# SCH_MSP430G2553-protoboard.net
KiCad netlist of a schematic drawn in EasyEDA
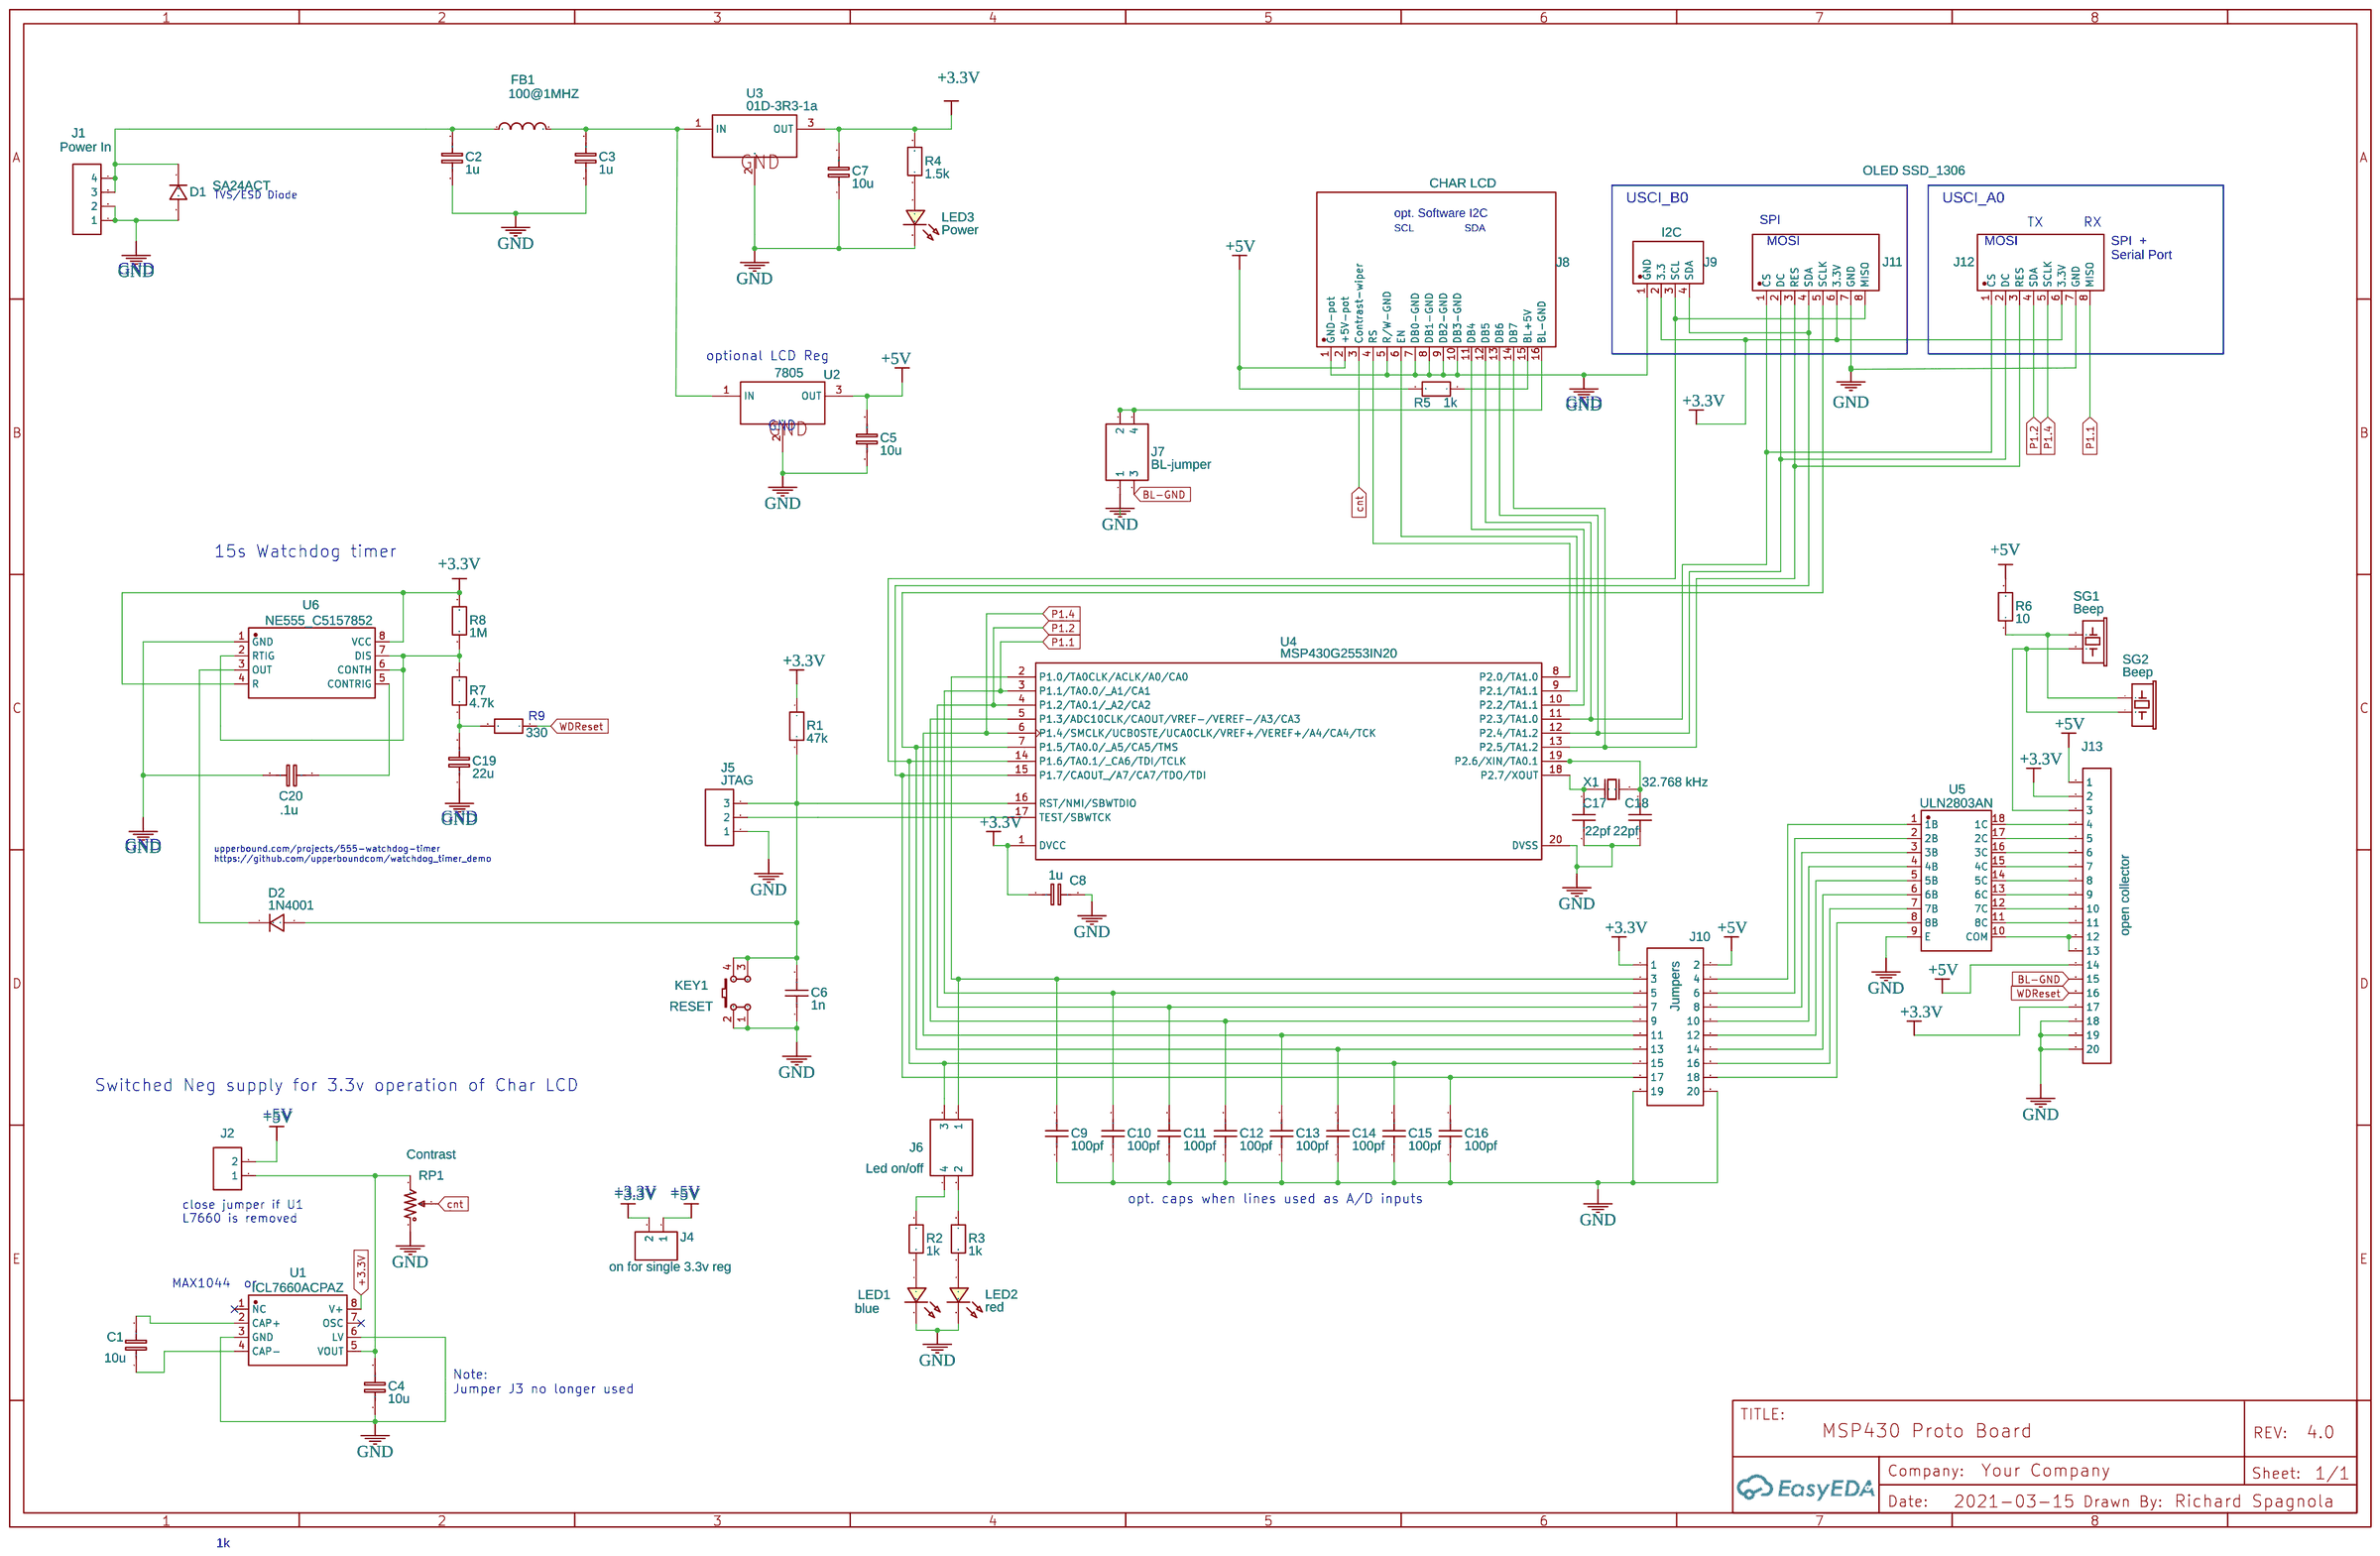
[diagram p0: schematic sheet]

(export (version "E")
  (design (tool "Eeschema 10.0.6"))
  (components
    (comp (ref "C1") (value "10u") (libsource (lib "") (part "C_RAD-0.2_EU_3")))
    (comp (ref "C2") (value "1u") (libsource (lib "") (part "C_RAD-0.2_EU")))
    (comp (ref "C3") (value "1u") (libsource (lib "") (part "C_RAD-0.2_EU")))
    (comp (ref "C4") (value "10u") (libsource (lib "") (part "C_RAD-0.2_EU")))
    (comp (ref "C5") (value "10u") (libsource (lib "") (part "C_RAD-0.2_EU_2")))
    (comp (ref "C6") (value "1n") (libsource (lib "") (part "C_RAD-0.1_US")))
    (comp (ref "C7") (value "10u") (libsource (lib "") (part "C_RAD-0.2_EU_2")))
    (comp (ref "C8") (value "1u") (libsource (lib "") (part "C_RAD-0.2_EU_4")))
    (comp (ref "C9") (value "100pf") (libsource (lib "") (part "C_RAD-0.1_US")))
    (comp (ref "C10") (value "100pf") (libsource (lib "") (part "C_RAD-0.1_US")))
    (comp (ref "C11") (value "100pf") (libsource (lib "") (part "C_RAD-0.1_US")))
    (comp (ref "C12") (value "100pf") (libsource (lib "") (part "C_RAD-0.1_US")))
    (comp (ref "C13") (value "100pf") (libsource (lib "") (part "C_RAD-0.1_US")))
    (comp (ref "C14") (value "100pf") (libsource (lib "") (part "C_RAD-0.1_US")))
    (comp (ref "C15") (value "100pf") (libsource (lib "") (part "C_RAD-0.1_US")))
    (comp (ref "C16") (value "100pf") (libsource (lib "") (part "C_RAD-0.1_US")))
    (comp (ref "C17") (value "22pf") (libsource (lib "") (part "C_RAD-0.1_US_1")))
    (comp (ref "C18") (value "22pf") (libsource (lib "") (part "C_RAD-0.1_US")))
    (comp (ref "C19") (value "22u") (libsource (lib "") (part "C_RAD-0.2_EU")))
    (comp (ref "C20") (value ".1u") (libsource (lib "") (part "C_RAD-0.2_EU_1")))
    (comp (ref "D1")
      (value "SA24ACT")
      (fields (field (name "BOM_Manufacturer Part") "1N4007") (field (name "BOM_Supplier Part") "C106903"))
      (libsource (lib "") (part "1N4007_1"))
    )
    (comp (ref "D2")
      (value "1N4001")
      (fields (field (name "BOM_Manufacturer Part") "1N4007") (field (name "BOM_Supplier Part") "C106903"))
      (libsource (lib "") (part "1N4007"))
    )
    (comp (ref "FB1")
      (value "100@1MHZ")
      (fields
        (field (name "BOM_Manufacturer Part") "MLB6*10-3T(f)")
        (field (name "BOM_Supplier Part") "C59501")
      )
      (libsource (lib "") (part "6Hole beads6*10-3T"))
    )
    (comp (ref "J1")
      (value "Power In")
      (fields (field (name "BOM_Supplier Part") "C124378"))
      (libsource (lib "") (part "HDR-M-2.54_1x4"))
    )
    (comp (ref "J2")
      (value "HDR-M-2.54_1x2")
      (fields (field (name "BOM_Supplier Part") "C124375"))
      (libsource (lib "") (part "HDR-M-2.54_1x2_1"))
    )
    (comp (ref "J4")
      (value "on for single 3.3v reg")
      (fields (field (name "BOM_Supplier Part") "C124375"))
      (libsource (lib "") (part "HDR-M-2.54_1x2"))
    )
    (comp (ref "J5")
      (value "JTAG")
      (fields (field (name "BOM_Supplier Part") "C180248"))
      (libsource (lib "") (part "HDR-M-2.54_1x3"))
    )
    (comp (ref "J6")
      (value "Led on/off")
      (fields (field (name "BOM_Supplier Part") "C66690"))
      (libsource (lib "") (part "HDR-M-2.54_2x2_1"))
    )
    (comp (ref "J7")
      (value "BL-jumper")
      (fields (field (name "BOM_Supplier Part") "C66690"))
      (libsource (lib "") (part "HDR-M-2.54_2x2"))
    )
    (comp (ref "J8") (value "CHAR LCD") (libsource (lib "") (part "LCD")))
    (comp (ref "J9") (value "I2C") (libsource (lib "") (part "I2C")))
    (comp (ref "J10")
      (value "Jumpers")
      (fields (field (name "BOM_Supplier Part") "C124359"))
      (libsource (lib "") (part "HDR-M-2.54_2x10"))
    )
    (comp (ref "J11") (value "OLED SSD_1306") (libsource (lib "") (part "SSD_1306")))
    (comp (ref "J12") (value "OLED SSD_1306") (libsource (lib "") (part "SSD_1306")))
    (comp (ref "J13")
      (value "open collector")
      (fields (field (name "BOM_Supplier Part") "C50981"))
      (libsource (lib "") (part "HDR-M-2.54_1x20"))
    )
    (comp (ref "KEY1")
      (value "RESET")
      (fields
        (field (name "BOM_Manufacturer Part") "K2-1102DP-E4SW-04")
        (field (name "BOM_Supplier Part") "C136684")
      )
      (libsource (lib "") (part "K4-6×6_TH"))
    )
    (comp (ref "LED1") (value "blue") (libsource (lib "") (part "LED-TH-5mm_B")))
    (comp (ref "LED2")
      (value "red")
      (fields
        (field (name "BOM_Manufacturer Part") "333-2SURD/S530-A3")
        (field (name "BOM_Supplier Part") "C87271")
      )
      (libsource (lib "") (part "LED-TH-5mm_R"))
    )
    (comp (ref "LED3")
      (value "Power")
      (fields
        (field (name "BOM_Manufacturer Part") "333-2SYGD/S530-E2")
        (field (name "BOM_Supplier Part") "C88163")
      )
      (libsource (lib "") (part "LED-TH-5mm_G"))
    )
    (comp (ref "R1") (value "47k") (libsource (lib "") (part "R_AXIAL-0.3_EU")))
    (comp (ref "R2") (value "1k") (libsource (lib "") (part "R_AXIAL-0.4_EU")))
    (comp (ref "R3") (value "1k") (libsource (lib "") (part "R_AXIAL-0.4_EU")))
    (comp (ref "R4") (value "1.5k") (libsource (lib "") (part "R_AXIAL-0.5_EU")))
    (comp (ref "R5") (value "1k") (libsource (lib "") (part "R_AXIAL-0.4_EU_1")))
    (comp (ref "R6") (value "10") (libsource (lib "") (part "R_AXIAL-0.4_EU")))
    (comp (ref "R7") (value "4.7k") (libsource (lib "") (part "R_AXIAL-0.4_EU")))
    (comp (ref "R8") (value "1M") (libsource (lib "") (part "R_AXIAL-0.4_EU")))
    (comp (ref "R10") (value "330") (libsource (lib "") (part "R_AXIAL-0.4_EU_1")))
    (comp (ref "RP1") (value "Contrast") (libsource (lib "") (part "R_3386P_US")))
    (comp (ref "SG1") (value "Beep") (libsource (lib "") (part "BUZZER_1")))
    (comp (ref "SG2") (value "Beep") (libsource (lib "") (part "BUZZER")))
    (comp (ref "U1")
      (value "ICL7660ACPAZ")
      (fields (field (name "BOM_Supplier Part") "C1356059"))
      (libsource (lib "") (part "ICL7660ACPAZ"))
    )
    (comp (ref "U2")
      (value "7805")
      (fields (field (name "BOM_Manufacturer Part") "L7805CV-DG") (field (name "BOM_Supplier Part") "C3795"))
      (libsource (lib "") (part "7805(TO-220)"))
    )
    (comp (ref "U3")
      (value "01D-3R3-1a")
      (fields (field (name "BOM_Manufacturer Part") "L7805CV-DG") (field (name "BOM_Supplier Part") "C3795"))
      (libsource (lib "") (part "7805(TO-220)"))
    )
    (comp (ref "U4")
      (value "MSP430G2553IN20")
      (fields (field (name "BOM_Supplier Part") "C201660"))
      (libsource (lib "") (part "MSP430G2553IN20"))
    )
    (comp (ref "U5")
      (value "ULN2803AN")
      (fields (field (name "BOM_Supplier Part") "C481685"))
      (libsource (lib "") (part "ULN2803AN"))
    )
    (comp (ref "U6")
      (value "NE555_C5157852")
      (fields (field (name "BOM_Manufacturer Part") "NE555") (field (name "BOM_Supplier Part") "C5157852"))
      (libsource (lib "") (part "NE555_C5157852"))
    )
    (comp (ref "X1")
      (value "32.768 kHz")
      (fields
        (field (name "BOM_Manufacturer Part") "ESA16.0000F12M25F")
        (field (name "BOM_Supplier Part") "C353692")
      )
      (libsource (lib "") (part "ESA16.0000F12M25F"))
    )
  )
  (nets
    (net (code "1") (name "+3.3V") (class "Default")
      (node (ref "C7") (pin "2") (pinfunction "2_2") (pintype "unspecified"))
      (node (ref "C8") (pin "1") (pinfunction "1_1") (pintype "unspecified"))
      (node (ref "J10") (pin "1") (pinfunction "1_1") (pintype "unspecified"))
      (node (ref "J11") (pin "6") (pinfunction "3.3V_6") (pintype "unspecified"))
      (node (ref "J12") (pin "6") (pinfunction "3.3V_6") (pintype "unspecified"))
      (node (ref "J13") (pin "17") (pinfunction "17_17") (pintype "unspecified"))
      (node (ref "J13") (pin "2") (pinfunction "2_2") (pintype "unspecified"))
      (node (ref "J4") (pin "2") (pinfunction "2_2") (pintype "unspecified"))
      (node (ref "J9") (pin "2") (pinfunction "3.3_2") (pintype "unspecified"))
      (node (ref "R1") (pin "1") (pinfunction "1_1") (pintype "unspecified"))
      (node (ref "R4") (pin "2") (pinfunction "2_2") (pintype "unspecified"))
      (node (ref "R8") (pin "2") (pinfunction "2_2") (pintype "unspecified"))
      (node (ref "U1") (pin "8") (pinfunction "V+_8") (pintype "unspecified"))
      (node (ref "U3") (pin "3") (pinfunction "OUT_3") (pintype "passive"))
      (node (ref "U4") (pin "1") (pinfunction "DVCC_1") (pintype "passive"))
      (node (ref "U6") (pin "4") (pinfunction "R_4") (pintype "unspecified"))
      (node (ref "U6") (pin "8") (pinfunction "VCC_8") (pintype "unspecified"))
    )
    (net (code "2") (name "+5V") (class "Default")
      (node (ref "C5") (pin "2") (pinfunction "2_2") (pintype "unspecified"))
      (node (ref "J10") (pin "2") (pinfunction "2_2") (pintype "unspecified"))
      (node (ref "J13") (pin "1") (pinfunction "1_1") (pintype "unspecified"))
      (node (ref "J13") (pin "14") (pinfunction "14_14") (pintype "unspecified"))
      (node (ref "J2") (pin "2") (pinfunction "2_2") (pintype "unspecified"))
      (node (ref "J4") (pin "1") (pinfunction "1_1") (pintype "unspecified"))
      (node (ref "J8") (pin "2") (pinfunction "+5V-pot_2") (pintype "unspecified"))
      (node (ref "R5") (pin "2") (pinfunction "2_2") (pintype "unspecified"))
      (node (ref "R6") (pin "2") (pinfunction "2_2") (pintype "unspecified"))
      (node (ref "U2") (pin "3") (pinfunction "OUT_3") (pintype "passive"))
    )
    (net (code "3") (name "BL-GND") (class "Default")
      (node (ref "J13") (pin "15") (pinfunction "15_15") (pintype "unspecified"))
      (node (ref "J7") (pin "3") (pinfunction "3_3") (pintype "input"))
    )
    (net (code "4") (name "GND") (class "Default")
      (node (ref "C10") (pin "1") (pinfunction "1_1") (pintype "unspecified"))
      (node (ref "C11") (pin "1") (pinfunction "1_1") (pintype "unspecified"))
      (node (ref "C12") (pin "1") (pinfunction "1_1") (pintype "unspecified"))
      (node (ref "C13") (pin "1") (pinfunction "1_1") (pintype "unspecified"))
      (node (ref "C14") (pin "1") (pinfunction "1_1") (pintype "unspecified"))
      (node (ref "C15") (pin "1") (pinfunction "1_1") (pintype "unspecified"))
      (node (ref "C16") (pin "1") (pinfunction "1_1") (pintype "unspecified"))
      (node (ref "C17") (pin "2") (pinfunction "2_2") (pintype "unspecified"))
      (node (ref "C18") (pin "1") (pinfunction "1_1") (pintype "unspecified"))
      (node (ref "C19") (pin "1") (pinfunction "1_1") (pintype "unspecified"))
      (node (ref "C2") (pin "1") (pinfunction "1_1") (pintype "unspecified"))
      (node (ref "C20") (pin "2") (pinfunction "2_2") (pintype "unspecified"))
      (node (ref "C3") (pin "1") (pinfunction "1_1") (pintype "unspecified"))
      (node (ref "C4") (pin "1") (pinfunction "1_1") (pintype "unspecified"))
      (node (ref "C5") (pin "1") (pinfunction "1_1") (pintype "unspecified"))
      (node (ref "C6") (pin "1") (pinfunction "1_1") (pintype "unspecified"))
      (node (ref "C7") (pin "1") (pinfunction "1_1") (pintype "unspecified"))
      (node (ref "C8") (pin "2") (pinfunction "2_2") (pintype "unspecified"))
      (node (ref "C9") (pin "1") (pinfunction "1_1") (pintype "unspecified"))
      (node (ref "D1") (pin "2") (pinfunction "2_2") (pintype "unspecified"))
      (node (ref "J1") (pin "1") (pinfunction "1_1") (pintype "unspecified"))
      (node (ref "J1") (pin "2") (pinfunction "2_2") (pintype "unspecified"))
      (node (ref "J10") (pin "19") (pinfunction "19_19") (pintype "unspecified"))
      (node (ref "J10") (pin "20") (pinfunction "20_20") (pintype "unspecified"))
      (node (ref "J11") (pin "7") (pinfunction "GND_7") (pintype "unspecified"))
      (node (ref "J12") (pin "7") (pinfunction "GND_7") (pintype "unspecified"))
      (node (ref "J13") (pin "18") (pinfunction "18_18") (pintype "unspecified"))
      (node (ref "J13") (pin "19") (pinfunction "19_19") (pintype "unspecified"))
      (node (ref "J13") (pin "20") (pinfunction "20_20") (pintype "unspecified"))
      (node (ref "J5") (pin "1") (pinfunction "1_1") (pintype "input"))
      (node (ref "J7") (pin "1") (pinfunction "1_1") (pintype "input"))
      (node (ref "J8") (pin "1") (pinfunction "GND-pot_1") (pintype "unspecified"))
      (node (ref "J8") (pin "10") (pinfunction "DB3-GND_10") (pintype "unspecified"))
      (node (ref "J8") (pin "5") (pinfunction "R/W-GND_5") (pintype "unspecified"))
      (node (ref "J8") (pin "7") (pinfunction "DB0-GND_7") (pintype "unspecified"))
      (node (ref "J8") (pin "8") (pinfunction "DB1-GND_8") (pintype "unspecified"))
      (node (ref "J8") (pin "9") (pinfunction "DB2-GND_9") (pintype "unspecified"))
      (node (ref "J9") (pin "1") (pinfunction "GND_1") (pintype "unspecified"))
      (node (ref "KEY1") (pin "1") (pinfunction "1_1") (pintype "unspecified"))
      (node (ref "KEY1") (pin "2") (pinfunction "2_2") (pintype "unspecified"))
      (node (ref "LED1") (pin "2") (pinfunction "2_2") (pintype "unspecified"))
      (node (ref "LED2") (pin "2") (pinfunction "2_2") (pintype "unspecified"))
      (node (ref "LED3") (pin "2") (pinfunction "2_2") (pintype "unspecified"))
      (node (ref "RP1") (pin "1") (pinfunction "1_1") (pintype "unspecified"))
      (node (ref "U1") (pin "3") (pinfunction "GND_3") (pintype "unspecified"))
      (node (ref "U1") (pin "6") (pinfunction "LV_6") (pintype "unspecified"))
      (node (ref "U2") (pin "2") (pinfunction "GND_2") (pintype "passive"))
      (node (ref "U3") (pin "2") (pinfunction "GND_2") (pintype "passive"))
      (node (ref "U4") (pin "20") (pinfunction "DVSS_20") (pintype "passive"))
      (node (ref "U5") (pin "9") (pinfunction "E_9") (pintype "unspecified"))
      (node (ref "U6") (pin "1") (pinfunction "GND_1") (pintype "unspecified"))
    )
    (net (code "5") (name "Net-(C2-Pad2)") (class "Default")
      (node (ref "C2") (pin "2") (pinfunction "2_2") (pintype "unspecified"))
      (node (ref "D1") (pin "1") (pinfunction "1_1") (pintype "unspecified"))
      (node (ref "FB1") (pin "1") (pinfunction "1_1") (pintype "unspecified"))
      (node (ref "J1") (pin "3") (pinfunction "3_3") (pintype "unspecified"))
      (node (ref "J1") (pin "4") (pinfunction "4_4") (pintype "unspecified"))
    )
    (net (code "6") (name "Net-(C19-Pad2)") (class "Default")
      (node (ref "C19") (pin "2") (pinfunction "2_2") (pintype "unspecified"))
      (node (ref "R10") (pin "2") (pinfunction "2_2") (pintype "unspecified"))
      (node (ref "R7") (pin "1") (pinfunction "1_1") (pintype "unspecified"))
    )
    (net (code "7") (name "Net-(J6-Pad2)") (class "Default")
      (node (ref "J6") (pin "2") (pinfunction "2_2") (pintype "input"))
      (node (ref "R3") (pin "2") (pinfunction "2_2") (pintype "unspecified"))
    )
    (net (code "8") (name "Net-(J6-Pad4)") (class "Default")
      (node (ref "J6") (pin "4") (pinfunction "4_4") (pintype "input"))
      (node (ref "R2") (pin "2") (pinfunction "2_2") (pintype "unspecified"))
    )
    (net (code "9") (name "Net-(J8-BL+5V)") (class "Default")
      (node (ref "J8") (pin "15") (pinfunction "BL+5V_15") (pintype "unspecified"))
      (node (ref "R5") (pin "1") (pinfunction "1_1") (pintype "unspecified"))
    )
    (net (code "10") (name "Net-(J8-BL-GND)") (class "Default")
      (node (ref "J7") (pin "2") (pinfunction "2_2") (pintype "input"))
      (node (ref "J7") (pin "4") (pinfunction "4_4") (pintype "input"))
      (node (ref "J8") (pin "16") (pinfunction "BL-GND_16") (pintype "unspecified"))
    )
    (net (code "11") (name "Net-(J8-DB4)") (class "Default")
      (node (ref "J8") (pin "11") (pinfunction "DB4_11") (pintype "unspecified"))
      (node (ref "U4") (pin "10") (pinfunction "P2.2/TA1.1_10") (pintype "bidirectional"))
    )
    (net (code "12") (name "Net-(J8-EN)") (class "Default")
      (node (ref "J8") (pin "6") (pinfunction "EN_6") (pintype "unspecified"))
      (node (ref "U4") (pin "9") (pinfunction "P2.1/TA1.1_9") (pintype "bidirectional"))
    )
    (net (code "13") (name "Net-(J8-RS)") (class "Default")
      (node (ref "J8") (pin "4") (pinfunction "RS_4") (pintype "unspecified"))
      (node (ref "U4") (pin "8") (pinfunction "P2.0/TA1.0_8") (pintype "bidirectional"))
    )
    (net (code "14") (name "Net-(J11-CS)") (class "Default")
      (node (ref "J11") (pin "1") (pinfunction "CS_1") (pintype "unspecified"))
      (node (ref "J12") (pin "1") (pinfunction "CS_1") (pintype "unspecified"))
      (node (ref "J8") (pin "12") (pinfunction "DB5_12") (pintype "unspecified"))
      (node (ref "U4") (pin "11") (pinfunction "P2.3/TA1.0_11") (pintype "bidirectional"))
    )
    (net (code "15") (name "Net-(J11-DC)") (class "Default")
      (node (ref "J11") (pin "2") (pinfunction "DC_2") (pintype "unspecified"))
      (node (ref "J12") (pin "2") (pinfunction "DC_2") (pintype "unspecified"))
      (node (ref "J8") (pin "13") (pinfunction "DB6_13") (pintype "unspecified"))
      (node (ref "U4") (pin "12") (pinfunction "P2.4/TA1.2_12") (pintype "bidirectional"))
    )
    (net (code "16") (name "Net-(J11-MISO)") (class "Default")
      (node (ref "C15") (pin "2") (pinfunction "2_2") (pintype "unspecified"))
      (node (ref "J10") (pin "15") (pinfunction "15_15") (pintype "unspecified"))
      (node (ref "J11") (pin "8") (pinfunction "MISO_8") (pintype "unspecified"))
      (node (ref "J6") (pin "3") (pinfunction "3_3") (pintype "input"))
      (node (ref "J9") (pin "3") (pinfunction "SCL_3") (pintype "unspecified"))
      (node (ref "U4") (pin "14") (pinfunction "P1.6/TA0.1/_CA6/TDI/TCLK_14") (pintype "bidirectional"))
    )
    (net (code "17") (name "Net-(J11-RES)") (class "Default")
      (node (ref "J11") (pin "3") (pinfunction "RES_3") (pintype "unspecified"))
      (node (ref "J12") (pin "3") (pinfunction "RES_3") (pintype "unspecified"))
      (node (ref "J8") (pin "14") (pinfunction "DB7_14") (pintype "unspecified"))
      (node (ref "U4") (pin "13") (pinfunction "P2.5/TA1.2_13") (pintype "bidirectional"))
    )
    (net (code "18") (name "Net-(J11-SCLK)") (class "Default")
      (node (ref "C14") (pin "2") (pinfunction "2_2") (pintype "unspecified"))
      (node (ref "J10") (pin "13") (pinfunction "13_13") (pintype "unspecified"))
      (node (ref "J11") (pin "5") (pinfunction "SCLK_5") (pintype "unspecified"))
      (node (ref "U4") (pin "7") (pinfunction "P1.5/TA0.0/_A5/CA5/TMS_7") (pintype "bidirectional"))
    )
    (net (code "19") (name "Net-(J11-SDA)") (class "Default")
      (node (ref "C16") (pin "2") (pinfunction "2_2") (pintype "unspecified"))
      (node (ref "J10") (pin "17") (pinfunction "17_17") (pintype "unspecified"))
      (node (ref "J11") (pin "4") (pinfunction "SDA_4") (pintype "unspecified"))
      (node (ref "J9") (pin "4") (pinfunction "SDA_4") (pintype "unspecified"))
      (node (ref "U4") (pin "15") (pinfunction "P1.7/CAOUT_/A7/CA7/TDO/TDI_15") (pintype "bidirectional"))
    )
    (net (code "20") (name "Net-(LED1-Pad1)") (class "Default")
      (node (ref "LED1") (pin "1") (pinfunction "1_1") (pintype "unspecified"))
      (node (ref "R2") (pin "1") (pinfunction "1_1") (pintype "unspecified"))
    )
    (net (code "21") (name "Net-(LED2-Pad1)") (class "Default")
      (node (ref "LED2") (pin "1") (pinfunction "1_1") (pintype "unspecified"))
      (node (ref "R3") (pin "1") (pinfunction "1_1") (pintype "unspecified"))
    )
    (net (code "22") (name "Net-(LED3-Pad1)") (class "Default")
      (node (ref "LED3") (pin "1") (pinfunction "1_1") (pintype "unspecified"))
      (node (ref "R4") (pin "1") (pinfunction "1_1") (pintype "unspecified"))
    )
    (net (code "23") (name "Net-(SG2-1)") (class "Default")
      (node (ref "R6") (pin "1") (pinfunction "1_1") (pintype "unspecified"))
      (node (ref "SG1") (pin "1") (pinfunction "1_1") (pintype "unspecified"))
      (node (ref "SG2") (pin "+") (pinfunction "1_+") (pintype "unspecified"))
    )
    (net (code "24") (name "Net-(SG2-2)") (class "Default")
      (node (ref "J13") (pin "3") (pinfunction "3_3") (pintype "unspecified"))
      (node (ref "SG1") (pin "2") (pinfunction "2_2") (pintype "unspecified"))
      (node (ref "SG2") (pin "-") (pinfunction "2_-") (pintype "unspecified"))
    )
    (net (code "25") (name "Net-(U1-CAP+)") (class "Default")
      (node (ref "C1") (pin "2") (pinfunction "2_2") (pintype "unspecified"))
      (node (ref "U1") (pin "2") (pinfunction "CAP+_2") (pintype "unspecified"))
    )
    (net (code "26") (name "Net-(U1-CAP-)") (class "Default")
      (node (ref "C1") (pin "1") (pinfunction "1_1") (pintype "unspecified"))
      (node (ref "U1") (pin "4") (pinfunction "CAP-_4") (pintype "unspecified"))
    )
    (net (code "27") (name "Net-(U1-VOUT)") (class "Default")
      (node (ref "C4") (pin "2") (pinfunction "2_2") (pintype "unspecified"))
      (node (ref "J2") (pin "1") (pinfunction "1_1") (pintype "unspecified"))
      (node (ref "RP1") (pin "3") (pinfunction "3_3") (pintype "unspecified"))
      (node (ref "U1") (pin "5") (pinfunction "VOUT_5") (pintype "unspecified"))
    )
    (net (code "28") (name "Net-(U2-IN)") (class "Default")
      (node (ref "C3") (pin "2") (pinfunction "2_2") (pintype "unspecified"))
      (node (ref "FB1") (pin "2") (pinfunction "2_2") (pintype "unspecified"))
      (node (ref "U2") (pin "1") (pinfunction "IN_1") (pintype "passive"))
      (node (ref "U3") (pin "1") (pinfunction "IN_1") (pintype "passive"))
    )
    (net (code "29") (name "Net-(U4-P1.0{slash}TA0CLK{slash}ACLK{slash}A0{slash}CA0)") (class "Default")
      (node (ref "C9") (pin "2") (pinfunction "2_2") (pintype "unspecified"))
      (node (ref "J10") (pin "3") (pinfunction "3_3") (pintype "unspecified"))
      (node (ref "J6") (pin "1") (pinfunction "1_1") (pintype "input"))
      (node (ref "U4") (pin "2") (pinfunction "P1.0/TA0CLK/ACLK/A0/CA0_2") (pintype "bidirectional"))
    )
    (net (code "30") (name "Net-(U4-P1.3{slash}ADC10CLK{slash}CAOUT{slash}VREF-{slash}VEREF-{slash}A3{slash}CA3)") (class "Default")
      (node (ref "C12") (pin "2") (pinfunction "2_2") (pintype "unspecified"))
      (node (ref "J10") (pin "9") (pinfunction "9_9") (pintype "unspecified"))
      (node (ref "U4") (pin "5") (pinfunction "P1.3/ADC10CLK/CAOUT/VREF-/VEREF-/A3/CA3_5") (pintype "bidirectional"))
    )
    (net (code "31") (name "Net-(U4-P2.6{slash}XIN{slash}TA0.1)") (class "Default")
      (node (ref "C18") (pin "2") (pinfunction "2_2") (pintype "unspecified"))
      (node (ref "U4") (pin "19") (pinfunction "P2.6/XIN/TA0.1_19") (pintype "bidirectional"))
      (node (ref "X1") (pin "2") (pinfunction "OSC2_2") (pintype "input"))
    )
    (net (code "32") (name "Net-(U4-P2.7{slash}XOUT)") (class "Default")
      (node (ref "C17") (pin "1") (pinfunction "1_1") (pintype "unspecified"))
      (node (ref "U4") (pin "18") (pinfunction "P2.7/XOUT_18") (pintype "bidirectional"))
      (node (ref "X1") (pin "1") (pinfunction "OSC1_1") (pintype "input"))
    )
    (net (code "33") (name "Net-(U4-RST{slash}NMI{slash}SBWTDIO)") (class "Default")
      (node (ref "C6") (pin "2") (pinfunction "2_2") (pintype "unspecified"))
      (node (ref "D2") (pin "2") (pinfunction "2_2") (pintype "unspecified"))
      (node (ref "J5") (pin "3") (pinfunction "3_3") (pintype "input"))
      (node (ref "KEY1") (pin "3") (pinfunction "3_3") (pintype "unspecified"))
      (node (ref "KEY1") (pin "4") (pinfunction "4_4") (pintype "unspecified"))
      (node (ref "R1") (pin "2") (pinfunction "2_2") (pintype "unspecified"))
      (node (ref "U4") (pin "16") (pinfunction "RST/NMI/SBWTDIO_16") (pintype "bidirectional"))
    )
    (net (code "34") (name "Net-(U4-TEST{slash}SBWTCK)") (class "Default")
      (node (ref "J5") (pin "2") (pinfunction "2_2") (pintype "input"))
      (node (ref "U4") (pin "17") (pinfunction "TEST/SBWTCK_17") (pintype "unspecified"))
    )
    (net (code "35") (name "Net-(U5-1B)") (class "Default")
      (node (ref "J10") (pin "4") (pinfunction "4_4") (pintype "unspecified"))
      (node (ref "U5") (pin "1") (pinfunction "1B_1") (pintype "unspecified"))
    )
    (net (code "36") (name "Net-(U5-1C)") (class "Default")
      (node (ref "J13") (pin "4") (pinfunction "4_4") (pintype "unspecified"))
      (node (ref "U5") (pin "18") (pinfunction "1C_18") (pintype "unspecified"))
    )
    (net (code "37") (name "Net-(U5-2B)") (class "Default")
      (node (ref "J10") (pin "6") (pinfunction "6_6") (pintype "unspecified"))
      (node (ref "U5") (pin "2") (pinfunction "2B_2") (pintype "unspecified"))
    )
    (net (code "38") (name "Net-(U5-2C)") (class "Default")
      (node (ref "J13") (pin "5") (pinfunction "5_5") (pintype "unspecified"))
      (node (ref "U5") (pin "17") (pinfunction "2C_17") (pintype "unspecified"))
    )
    (net (code "39") (name "Net-(U5-3B)") (class "Default")
      (node (ref "J10") (pin "8") (pinfunction "8_8") (pintype "unspecified"))
      (node (ref "U5") (pin "3") (pinfunction "3B_3") (pintype "unspecified"))
    )
    (net (code "40") (name "Net-(U5-3C)") (class "Default")
      (node (ref "J13") (pin "6") (pinfunction "6_6") (pintype "unspecified"))
      (node (ref "U5") (pin "16") (pinfunction "3C_16") (pintype "unspecified"))
    )
    (net (code "41") (name "Net-(U5-4B)") (class "Default")
      (node (ref "J10") (pin "10") (pinfunction "10_10") (pintype "unspecified"))
      (node (ref "U5") (pin "4") (pinfunction "4B_4") (pintype "unspecified"))
    )
    (net (code "42") (name "Net-(U5-4C)") (class "Default")
      (node (ref "J13") (pin "7") (pinfunction "7_7") (pintype "unspecified"))
      (node (ref "U5") (pin "15") (pinfunction "4C_15") (pintype "unspecified"))
    )
    (net (code "43") (name "Net-(U5-5B)") (class "Default")
      (node (ref "J10") (pin "12") (pinfunction "12_12") (pintype "unspecified"))
      (node (ref "U5") (pin "5") (pinfunction "5B_5") (pintype "unspecified"))
    )
    (net (code "44") (name "Net-(U5-5C)") (class "Default")
      (node (ref "J13") (pin "8") (pinfunction "8_8") (pintype "unspecified"))
      (node (ref "U5") (pin "14") (pinfunction "5C_14") (pintype "unspecified"))
    )
    (net (code "45") (name "Net-(U5-6B)") (class "Default")
      (node (ref "J10") (pin "14") (pinfunction "14_14") (pintype "unspecified"))
      (node (ref "U5") (pin "6") (pinfunction "6B_6") (pintype "unspecified"))
    )
    (net (code "46") (name "Net-(U5-6C)") (class "Default")
      (node (ref "J13") (pin "9") (pinfunction "9_9") (pintype "unspecified"))
      (node (ref "U5") (pin "13") (pinfunction "6C_13") (pintype "unspecified"))
    )
    (net (code "47") (name "Net-(U5-7B)") (class "Default")
      (node (ref "J10") (pin "16") (pinfunction "16_16") (pintype "unspecified"))
      (node (ref "U5") (pin "7") (pinfunction "7B_7") (pintype "unspecified"))
    )
    (net (code "48") (name "Net-(U5-7C)") (class "Default")
      (node (ref "J13") (pin "10") (pinfunction "10_10") (pintype "unspecified"))
      (node (ref "U5") (pin "12") (pinfunction "7C_12") (pintype "unspecified"))
    )
    (net (code "49") (name "Net-(U5-8B)") (class "Default")
      (node (ref "J10") (pin "18") (pinfunction "18_18") (pintype "unspecified"))
      (node (ref "U5") (pin "8") (pinfunction "8B_8") (pintype "unspecified"))
    )
    (net (code "50") (name "Net-(U5-8C)") (class "Default")
      (node (ref "J13") (pin "11") (pinfunction "11_11") (pintype "unspecified"))
      (node (ref "U5") (pin "11") (pinfunction "8C_11") (pintype "unspecified"))
    )
    (net (code "51") (name "Net-(U5-COM)") (class "Default")
      (node (ref "J13") (pin "12") (pinfunction "12_12") (pintype "unspecified"))
      (node (ref "J13") (pin "13") (pinfunction "13_13") (pintype "unspecified"))
      (node (ref "U5") (pin "10") (pinfunction "COM_10") (pintype "unspecified"))
    )
    (net (code "52") (name "Net-(U6-CONTH)") (class "Default")
      (node (ref "R7") (pin "2") (pinfunction "2_2") (pintype "unspecified"))
      (node (ref "R8") (pin "1") (pinfunction "1_1") (pintype "unspecified"))
      (node (ref "U6") (pin "2") (pinfunction "RTIG_2") (pintype "unspecified"))
      (node (ref "U6") (pin "6") (pinfunction "CONTH_6") (pintype "unspecified"))
      (node (ref "U6") (pin "7") (pinfunction "DIS_7") (pintype "unspecified"))
    )
    (net (code "53") (name "Net-(U6-CONTRIG)") (class "Default")
      (node (ref "C20") (pin "1") (pinfunction "1_1") (pintype "unspecified"))
      (node (ref "U6") (pin "5") (pinfunction "CONTRIG_5") (pintype "unspecified"))
    )
    (net (code "54") (name "Net-(U6-OUT)") (class "Default")
      (node (ref "D2") (pin "1") (pinfunction "1_1") (pintype "unspecified"))
      (node (ref "U6") (pin "3") (pinfunction "OUT_3") (pintype "unspecified"))
    )
    (net (code "55") (name "P1.1") (class "Default")
      (node (ref "C10") (pin "2") (pinfunction "2_2") (pintype "unspecified"))
      (node (ref "J10") (pin "5") (pinfunction "5_5") (pintype "unspecified"))
      (node (ref "J12") (pin "8") (pinfunction "MISO_8") (pintype "unspecified"))
      (node (ref "U4") (pin "3") (pinfunction "P1.1/TA0.0/_A1/CA1_3") (pintype "bidirectional"))
    )
    (net (code "56") (name "P1.2") (class "Default")
      (node (ref "C11") (pin "2") (pinfunction "2_2") (pintype "unspecified"))
      (node (ref "J10") (pin "7") (pinfunction "7_7") (pintype "unspecified"))
      (node (ref "J12") (pin "4") (pinfunction "SDA_4") (pintype "unspecified"))
      (node (ref "U4") (pin "4") (pinfunction "P1.2/TA0.1/_A2/CA2_4") (pintype "bidirectional"))
    )
    (net (code "57") (name "P1.4") (class "Default")
      (node (ref "C13") (pin "2") (pinfunction "2_2") (pintype "unspecified"))
      (node (ref "J10") (pin "11") (pinfunction "11_11") (pintype "unspecified"))
      (node (ref "J12") (pin "5") (pinfunction "SCLK_5") (pintype "unspecified"))
      (node (ref "U4") (pin "6") (pinfunction "P1.4/SMCLK/UCB0STE/UCA0CLK/VREF+/VEREF+/A4/CA4/TCK_6") (pintype "bidirectional"))
    )
    (net (code "58") (name "WDReset") (class "Default")
      (node (ref "J13") (pin "16") (pinfunction "16_16") (pintype "unspecified"))
      (node (ref "R10") (pin "1") (pinfunction "1_1") (pintype "unspecified"))
    )
    (net (code "59") (name "cnt") (class "Default")
      (node (ref "J8") (pin "3") (pinfunction "Contrast-wiper_3") (pintype "unspecified"))
      (node (ref "RP1") (pin "2") (pinfunction "2_2") (pintype "unspecified"))
    )
    (net (code "60") (name "unconnected-(U1-NC-Pad1)") (class "Default")
      (node (ref "U1") (pin "1") (pinfunction "NC_1") (pintype "unspecified+no_connect"))
    )
    (net (code "61") (name "unconnected-(U1-OSC-Pad7)") (class "Default")
      (node (ref "U1") (pin "7") (pinfunction "OSC_7") (pintype "unspecified+no_connect"))
    )
  )
)
